# 3DAGM.net
KiCad netlist of a schematic drawn in EAGLE
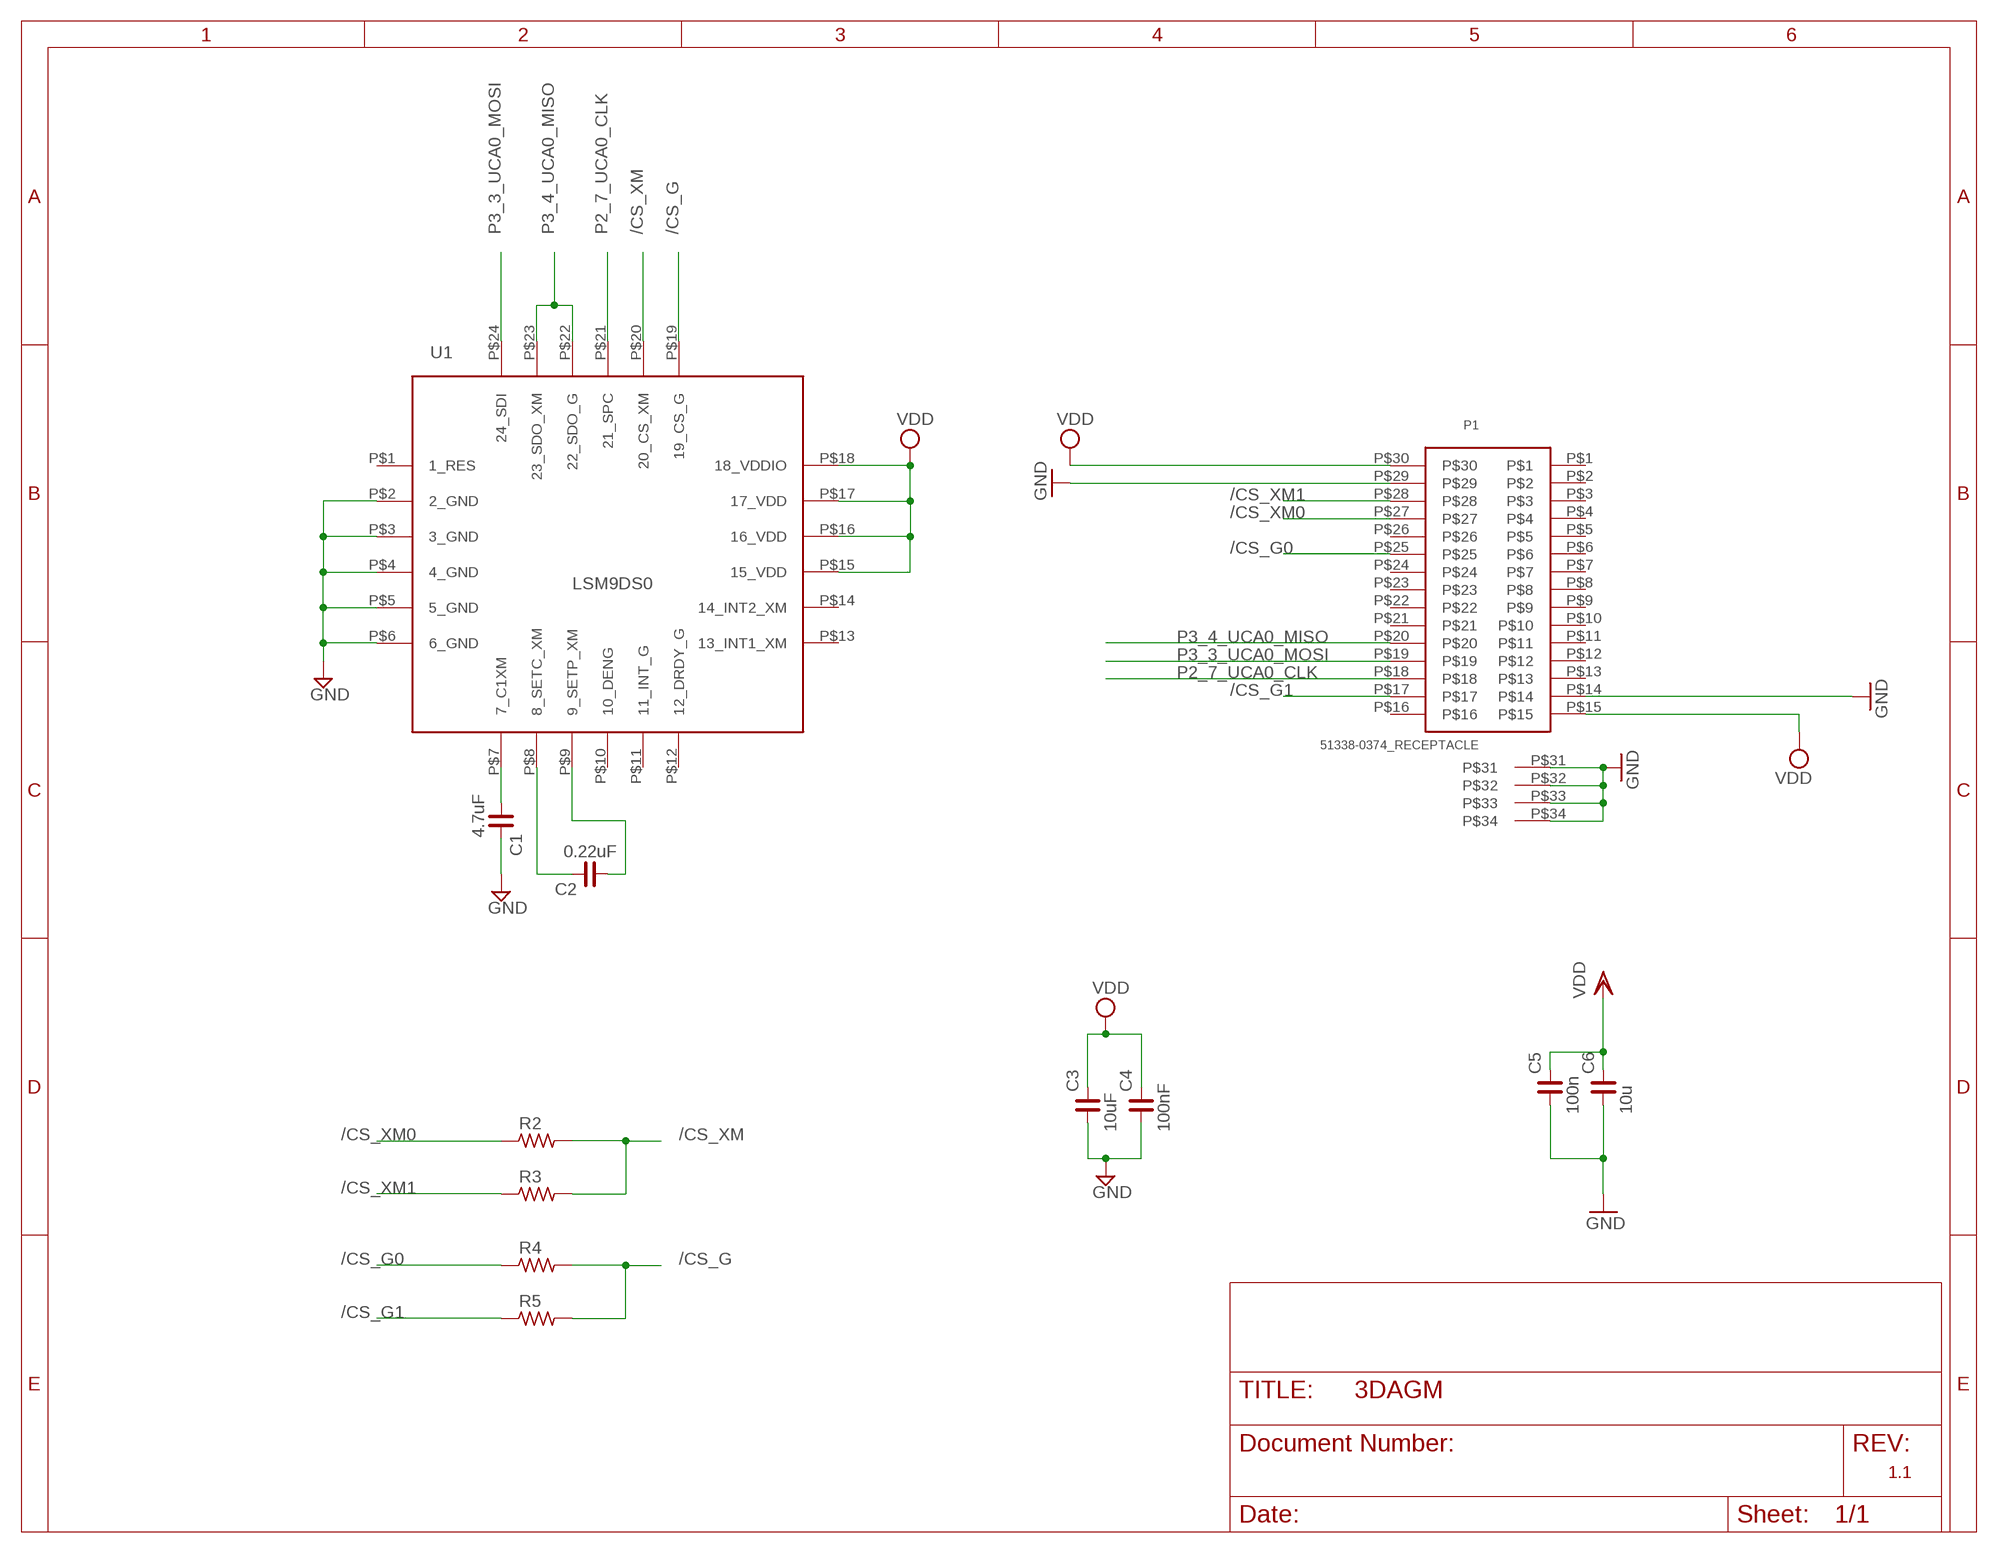
[diagram p0: schematic, sheet 1]

(export (version "E")
  (design (tool "Eeschema 10.0.6"))
  (components
    (comp (ref "C1")
      (value "4.7uF")
      (footprint "eagle-import:C0402")
      (libsource (lib "eagle-import") (part "C_0402"))
    )
    (comp (ref "C2")
      (value "0.22uF")
      (footprint "eagle-import:C0402")
      (libsource (lib "eagle-import") (part "C_0402"))
    )
    (comp (ref "C3")
      (value "10uF")
      (footprint "eagle-import:C0402")
      (libsource (lib "eagle-import") (part "C_0402"))
    )
    (comp (ref "C4")
      (value "100nF")
      (footprint "eagle-import:C0402")
      (libsource (lib "eagle-import") (part "C_0402"))
    )
    (comp (ref "C5")
      (value "100n")
      (footprint "eagle-import:C0402")
      (libsource (lib "eagle-import") (part "C_0402"))
    )
    (comp (ref "C6")
      (value "10u")
      (footprint "eagle-import:C0402")
      (libsource (lib "eagle-import") (part "C_0402"))
    )
    (comp (ref "P1")
      (value "51338-0374_RECEPTACLE")
      (footprint "eagle-import:51338-0374_RECEPTACLE")
      (libsource (lib "eagle-import") (part "51338-0374_RECEPTACLE"))
    )
    (comp (ref "R2")
      (value "R_0402")
      (footprint "eagle-import:R0402")
      (libsource (lib "eagle-import") (part "R_0402"))
    )
    (comp (ref "R3")
      (value "R_0402")
      (footprint "eagle-import:R0402")
      (libsource (lib "eagle-import") (part "R_0402"))
    )
    (comp (ref "R4")
      (value "R_0402")
      (footprint "eagle-import:R0402")
      (libsource (lib "eagle-import") (part "R_0402"))
    )
    (comp (ref "R5")
      (value "R_0402")
      (footprint "eagle-import:R0402")
      (libsource (lib "eagle-import") (part "R_0402"))
    )
    (comp (ref "U$1")
      (value "LSM9DS09DOFS0")
      (footprint "eagle-import:LGA24(4X4X1)")
      (libsource (lib "eagle-import") (part "LSM9DS09DOFS0"))
    )
  )
  (nets
    (net (code "1") (name "/P2_7_UCA0_CLK") (class "Default")
      (node (ref "P1") (pin "P$18") (pinfunction "P$18_P$18") (pintype "bidirectional"))
      (node (ref "U$1") (pin "P$21") (pinfunction "21_SPC_P$21") (pintype "bidirectional"))
    )
    (net (code "2") (name "/P3_3_UCA0_MOSI") (class "Default")
      (node (ref "P1") (pin "P$19") (pinfunction "P$19_P$19") (pintype "bidirectional"))
      (node (ref "U$1") (pin "P$24") (pinfunction "24_SDI_P$24") (pintype "bidirectional"))
    )
    (net (code "3") (name "/P3_4_UCA0_MISO") (class "Default")
      (node (ref "P1") (pin "P$20") (pinfunction "P$20_P$20") (pintype "bidirectional"))
      (node (ref "U$1") (pin "P$22") (pinfunction "22_SDO_G_P$22") (pintype "bidirectional"))
      (node (ref "U$1") (pin "P$23") (pinfunction "23_SDO_XM_P$23") (pintype "bidirectional"))
    )
    (net (code "4") (name "/{slash}CS_G") (class "Default")
      (node (ref "R4") (pin "2") (pinfunction "2_2") (pintype "passive"))
      (node (ref "R5") (pin "2") (pinfunction "2_2") (pintype "passive"))
      (node (ref "U$1") (pin "P$19") (pinfunction "19_CS_G_P$19") (pintype "bidirectional"))
    )
    (net (code "5") (name "/{slash}CS_G0") (class "Default")
      (node (ref "P1") (pin "P$25") (pinfunction "P$25_P$25") (pintype "bidirectional"))
      (node (ref "R4") (pin "1") (pinfunction "1_1") (pintype "passive"))
    )
    (net (code "6") (name "/{slash}CS_G1") (class "Default")
      (node (ref "P1") (pin "P$17") (pinfunction "P$17_P$17") (pintype "bidirectional"))
      (node (ref "R5") (pin "1") (pinfunction "1_1") (pintype "passive"))
    )
    (net (code "7") (name "/{slash}CS_XM") (class "Default")
      (node (ref "R2") (pin "2") (pinfunction "2_2") (pintype "passive"))
      (node (ref "R3") (pin "2") (pinfunction "2_2") (pintype "passive"))
      (node (ref "U$1") (pin "P$20") (pinfunction "20_CS_XM_P$20") (pintype "bidirectional"))
    )
    (net (code "8") (name "/{slash}CS_XM0") (class "Default")
      (node (ref "P1") (pin "P$27") (pinfunction "P$27_P$27") (pintype "bidirectional"))
      (node (ref "R2") (pin "1") (pinfunction "1_1") (pintype "passive"))
    )
    (net (code "9") (name "/{slash}CS_XM1") (class "Default")
      (node (ref "P1") (pin "P$28") (pinfunction "P$28_P$28") (pintype "bidirectional"))
      (node (ref "R3") (pin "1") (pinfunction "1_1") (pintype "passive"))
    )
    (net (code "10") (name "GND") (class "Default")
      (node (ref "C1") (pin "2") (pinfunction "2_2") (pintype "passive"))
      (node (ref "C3") (pin "1") (pinfunction "1_1") (pintype "passive"))
      (node (ref "C4") (pin "1") (pinfunction "1_1") (pintype "passive"))
      (node (ref "C5") (pin "1") (pinfunction "1_1") (pintype "passive"))
      (node (ref "C6") (pin "1") (pinfunction "1_1") (pintype "passive"))
      (node (ref "P1") (pin "P$14") (pinfunction "P$14_P$14") (pintype "bidirectional"))
      (node (ref "P1") (pin "P$29") (pinfunction "P$29_P$29") (pintype "bidirectional"))
      (node (ref "P1") (pin "P$31") (pinfunction "P$31_P$31") (pintype "bidirectional"))
      (node (ref "P1") (pin "P$32") (pinfunction "P$32_P$32") (pintype "bidirectional"))
      (node (ref "P1") (pin "P$33") (pinfunction "P$33_P$33") (pintype "bidirectional"))
      (node (ref "P1") (pin "P$34") (pinfunction "P$34_P$34") (pintype "bidirectional"))
      (node (ref "U$1") (pin "P$2") (pinfunction "2_GND_P$2") (pintype "bidirectional"))
      (node (ref "U$1") (pin "P$3") (pinfunction "3_GND_P$3") (pintype "bidirectional"))
      (node (ref "U$1") (pin "P$4") (pinfunction "4_GND_P$4") (pintype "bidirectional"))
      (node (ref "U$1") (pin "P$5") (pinfunction "5_GND_P$5") (pintype "bidirectional"))
      (node (ref "U$1") (pin "P$6") (pinfunction "6_GND_P$6") (pintype "bidirectional"))
    )
    (net (code "11") (name "Net-(U$1-7_C1XM)") (class "Default")
      (node (ref "C1") (pin "1") (pinfunction "1_1") (pintype "passive"))
      (node (ref "U$1") (pin "P$7") (pinfunction "7_C1XM_P$7") (pintype "bidirectional"))
    )
    (net (code "12") (name "Net-(U$1-8_SETC_XM)") (class "Default")
      (node (ref "C2") (pin "2") (pinfunction "2_2") (pintype "passive"))
      (node (ref "U$1") (pin "P$8") (pinfunction "8_SETC_XM_P$8") (pintype "bidirectional"))
    )
    (net (code "13") (name "Net-(U$1-9_SETP_XM)") (class "Default")
      (node (ref "C2") (pin "1") (pinfunction "1_1") (pintype "passive"))
      (node (ref "U$1") (pin "P$9") (pinfunction "9_SETP_XM_P$9") (pintype "bidirectional"))
    )
    (net (code "14") (name "VDD") (class "Default")
      (node (ref "C3") (pin "2") (pinfunction "2_2") (pintype "passive"))
      (node (ref "C4") (pin "2") (pinfunction "2_2") (pintype "passive"))
      (node (ref "C5") (pin "2") (pinfunction "2_2") (pintype "passive"))
      (node (ref "C6") (pin "2") (pinfunction "2_2") (pintype "passive"))
      (node (ref "P1") (pin "P$15") (pinfunction "P$15_P$15") (pintype "bidirectional"))
      (node (ref "P1") (pin "P$30") (pinfunction "P$30_P$30") (pintype "bidirectional"))
      (node (ref "U$1") (pin "P$15") (pinfunction "15_VDD_P$15") (pintype "bidirectional"))
      (node (ref "U$1") (pin "P$16") (pinfunction "16_VDD_P$16") (pintype "bidirectional"))
      (node (ref "U$1") (pin "P$17") (pinfunction "17_VDD_P$17") (pintype "bidirectional"))
      (node (ref "U$1") (pin "P$18") (pinfunction "18_VDDIO_P$18") (pintype "bidirectional"))
    )
    (net (code "15") (name "unconnected-(P1-PadP$1)") (class "Default")
      (node (ref "P1") (pin "P$1") (pinfunction "P$1_P$1") (pintype "bidirectional"))
    )
    (net (code "16") (name "unconnected-(P1-PadP$2)") (class "Default")
      (node (ref "P1") (pin "P$2") (pinfunction "P$2_P$2") (pintype "bidirectional"))
    )
    (net (code "17") (name "unconnected-(P1-PadP$3)") (class "Default")
      (node (ref "P1") (pin "P$3") (pinfunction "P$3_P$3") (pintype "bidirectional"))
    )
    (net (code "18") (name "unconnected-(P1-PadP$4)") (class "Default")
      (node (ref "P1") (pin "P$4") (pinfunction "P$4_P$4") (pintype "bidirectional"))
    )
    (net (code "19") (name "unconnected-(P1-PadP$5)") (class "Default")
      (node (ref "P1") (pin "P$5") (pinfunction "P$5_P$5") (pintype "bidirectional"))
    )
    (net (code "20") (name "unconnected-(P1-PadP$6)") (class "Default")
      (node (ref "P1") (pin "P$6") (pinfunction "P$6_P$6") (pintype "bidirectional"))
    )
    (net (code "21") (name "unconnected-(P1-PadP$7)") (class "Default")
      (node (ref "P1") (pin "P$7") (pinfunction "P$7_P$7") (pintype "bidirectional"))
    )
    (net (code "22") (name "unconnected-(P1-PadP$8)") (class "Default")
      (node (ref "P1") (pin "P$8") (pinfunction "P$8_P$8") (pintype "bidirectional"))
    )
    (net (code "23") (name "unconnected-(P1-PadP$9)") (class "Default")
      (node (ref "P1") (pin "P$9") (pinfunction "P$9_P$9") (pintype "bidirectional"))
    )
    (net (code "24") (name "unconnected-(P1-PadP$10)") (class "Default")
      (node (ref "P1") (pin "P$10") (pinfunction "P$10_P$10") (pintype "bidirectional"))
    )
    (net (code "25") (name "unconnected-(P1-PadP$11)") (class "Default")
      (node (ref "P1") (pin "P$11") (pinfunction "P$11_P$11") (pintype "bidirectional"))
    )
    (net (code "26") (name "unconnected-(P1-PadP$12)") (class "Default")
      (node (ref "P1") (pin "P$12") (pinfunction "P$12_P$12") (pintype "bidirectional"))
    )
    (net (code "27") (name "unconnected-(P1-PadP$13)") (class "Default")
      (node (ref "P1") (pin "P$13") (pinfunction "P$13_P$13") (pintype "bidirectional"))
    )
    (net (code "28") (name "unconnected-(P1-PadP$16)") (class "Default")
      (node (ref "P1") (pin "P$16") (pinfunction "P$16_P$16") (pintype "bidirectional"))
    )
    (net (code "29") (name "unconnected-(P1-PadP$21)") (class "Default")
      (node (ref "P1") (pin "P$21") (pinfunction "P$21_P$21") (pintype "bidirectional"))
    )
    (net (code "30") (name "unconnected-(P1-PadP$22)") (class "Default")
      (node (ref "P1") (pin "P$22") (pinfunction "P$22_P$22") (pintype "bidirectional"))
    )
    (net (code "31") (name "unconnected-(P1-PadP$23)") (class "Default")
      (node (ref "P1") (pin "P$23") (pinfunction "P$23_P$23") (pintype "bidirectional"))
    )
    (net (code "32") (name "unconnected-(P1-PadP$24)") (class "Default")
      (node (ref "P1") (pin "P$24") (pinfunction "P$24_P$24") (pintype "bidirectional"))
    )
    (net (code "33") (name "unconnected-(P1-PadP$26)") (class "Default")
      (node (ref "P1") (pin "P$26") (pinfunction "P$26_P$26") (pintype "bidirectional"))
    )
    (net (code "34") (name "unconnected-(U$1-1_RES-PadP$1)") (class "Default")
      (node (ref "U$1") (pin "P$1") (pinfunction "1_RES_P$1") (pintype "bidirectional"))
    )
    (net (code "35") (name "unconnected-(U$1-10_DENG-PadP$10)") (class "Default")
      (node (ref "U$1") (pin "P$10") (pinfunction "10_DENG_P$10") (pintype "bidirectional"))
    )
    (net (code "36") (name "unconnected-(U$1-11_INT_G-PadP$11)") (class "Default")
      (node (ref "U$1") (pin "P$11") (pinfunction "11_INT_G_P$11") (pintype "bidirectional"))
    )
    (net (code "37") (name "unconnected-(U$1-12_DRDY_G-PadP$12)") (class "Default")
      (node (ref "U$1") (pin "P$12") (pinfunction "12_DRDY_G_P$12") (pintype "bidirectional"))
    )
    (net (code "38") (name "unconnected-(U$1-13_INT1_XM-PadP$13)") (class "Default")
      (node (ref "U$1") (pin "P$13") (pinfunction "13_INT1_XM_P$13") (pintype "bidirectional"))
    )
    (net (code "39") (name "unconnected-(U$1-14_INT2_XM-PadP$14)") (class "Default")
      (node (ref "U$1") (pin "P$14") (pinfunction "14_INT2_XM_P$14") (pintype "bidirectional"))
    )
  )
)
